# parallel_paths_v1_0_100um.net
KiCad netlist of a schematic drawn in EAGLE
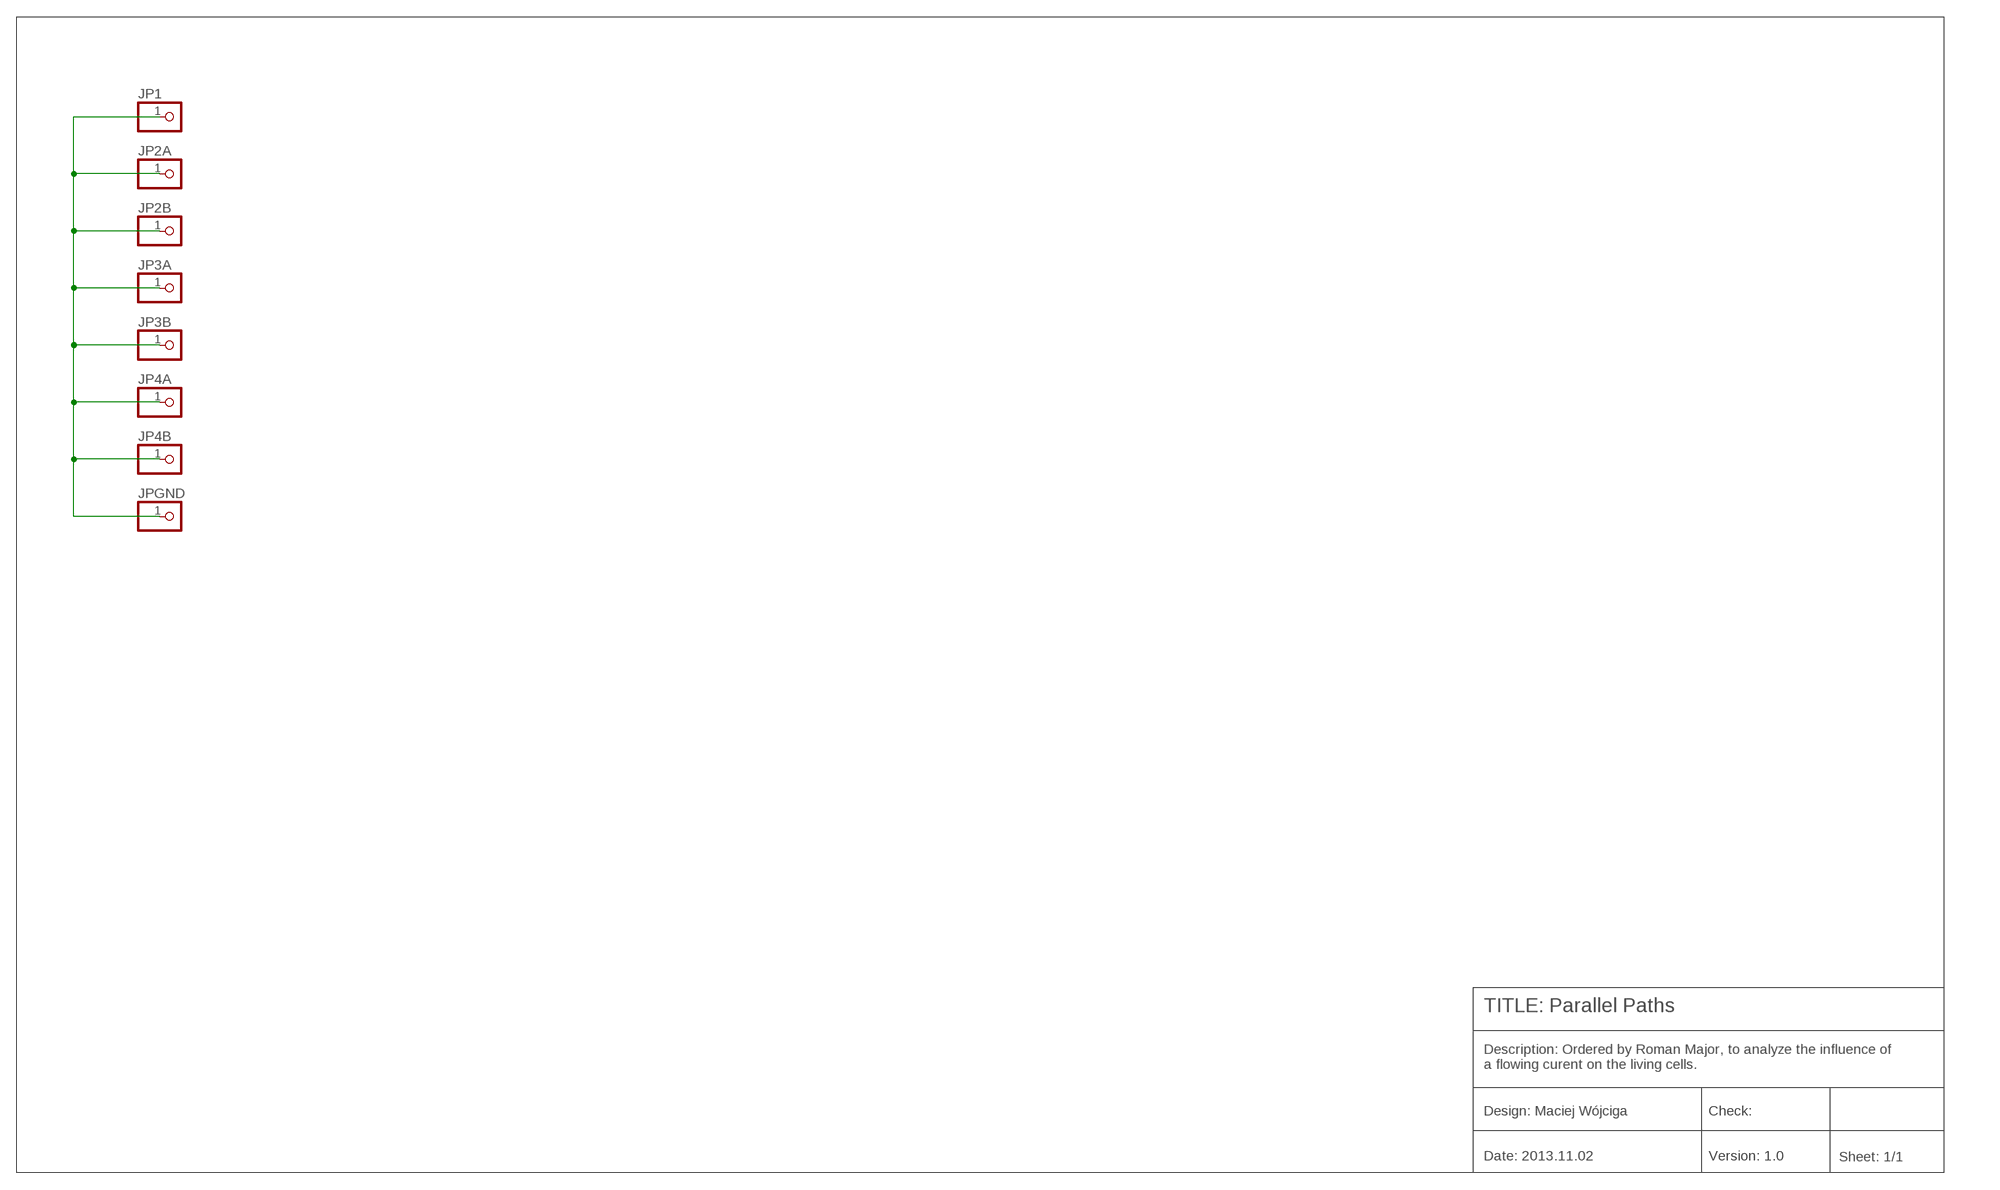
[diagram p0: schematic, sheet 1]

(export (version "E")
  (design (tool "Eeschema 10.0.6"))
  (components
    (comp (ref "JP1")
      (value "PINHD-1X1")
      (footprint "eagle-import:1X01")
      (libsource (lib "eagle-import") (part "PINHD-1X1"))
    )
    (comp (ref "JP2A")
      (value "PINHD-1X1")
      (footprint "eagle-import:1X01")
      (libsource (lib "eagle-import") (part "PINHD-1X1"))
    )
    (comp (ref "JP2B")
      (value "PINHD-1X1")
      (footprint "eagle-import:1X01")
      (libsource (lib "eagle-import") (part "PINHD-1X1"))
    )
    (comp (ref "JP3A")
      (value "PINHD-1X1")
      (footprint "eagle-import:1X01")
      (libsource (lib "eagle-import") (part "PINHD-1X1"))
    )
    (comp (ref "JP3B")
      (value "PINHD-1X1")
      (footprint "eagle-import:1X01")
      (libsource (lib "eagle-import") (part "PINHD-1X1"))
    )
    (comp (ref "JP4A")
      (value "PINHD-1X1")
      (footprint "eagle-import:1X01")
      (libsource (lib "eagle-import") (part "PINHD-1X1"))
    )
    (comp (ref "JP4B")
      (value "PINHD-1X1")
      (footprint "eagle-import:1X01")
      (libsource (lib "eagle-import") (part "PINHD-1X1"))
    )
    (comp (ref "JPGND")
      (value "PINHD-1X1")
      (footprint "eagle-import:1X01")
      (libsource (lib "eagle-import") (part "PINHD-1X1"))
    )
  )
  (nets
    (net (code "1") (name "Net-(JP1-Pad1)") (class "Default")
      (node (ref "JP1") (pin "1") (pinfunction "1_1") (pintype "passive"))
      (node (ref "JP2A") (pin "1") (pinfunction "1_1") (pintype "passive"))
      (node (ref "JP2B") (pin "1") (pinfunction "1_1") (pintype "passive"))
      (node (ref "JP3A") (pin "1") (pinfunction "1_1") (pintype "passive"))
      (node (ref "JP3B") (pin "1") (pinfunction "1_1") (pintype "passive"))
      (node (ref "JP4A") (pin "1") (pinfunction "1_1") (pintype "passive"))
      (node (ref "JP4B") (pin "1") (pinfunction "1_1") (pintype "passive"))
      (node (ref "JPGND") (pin "1") (pinfunction "1_1") (pintype "passive"))
    )
  )
)
